# DRV8301.net
KiCad netlist of a schematic drawn in Altium Designer
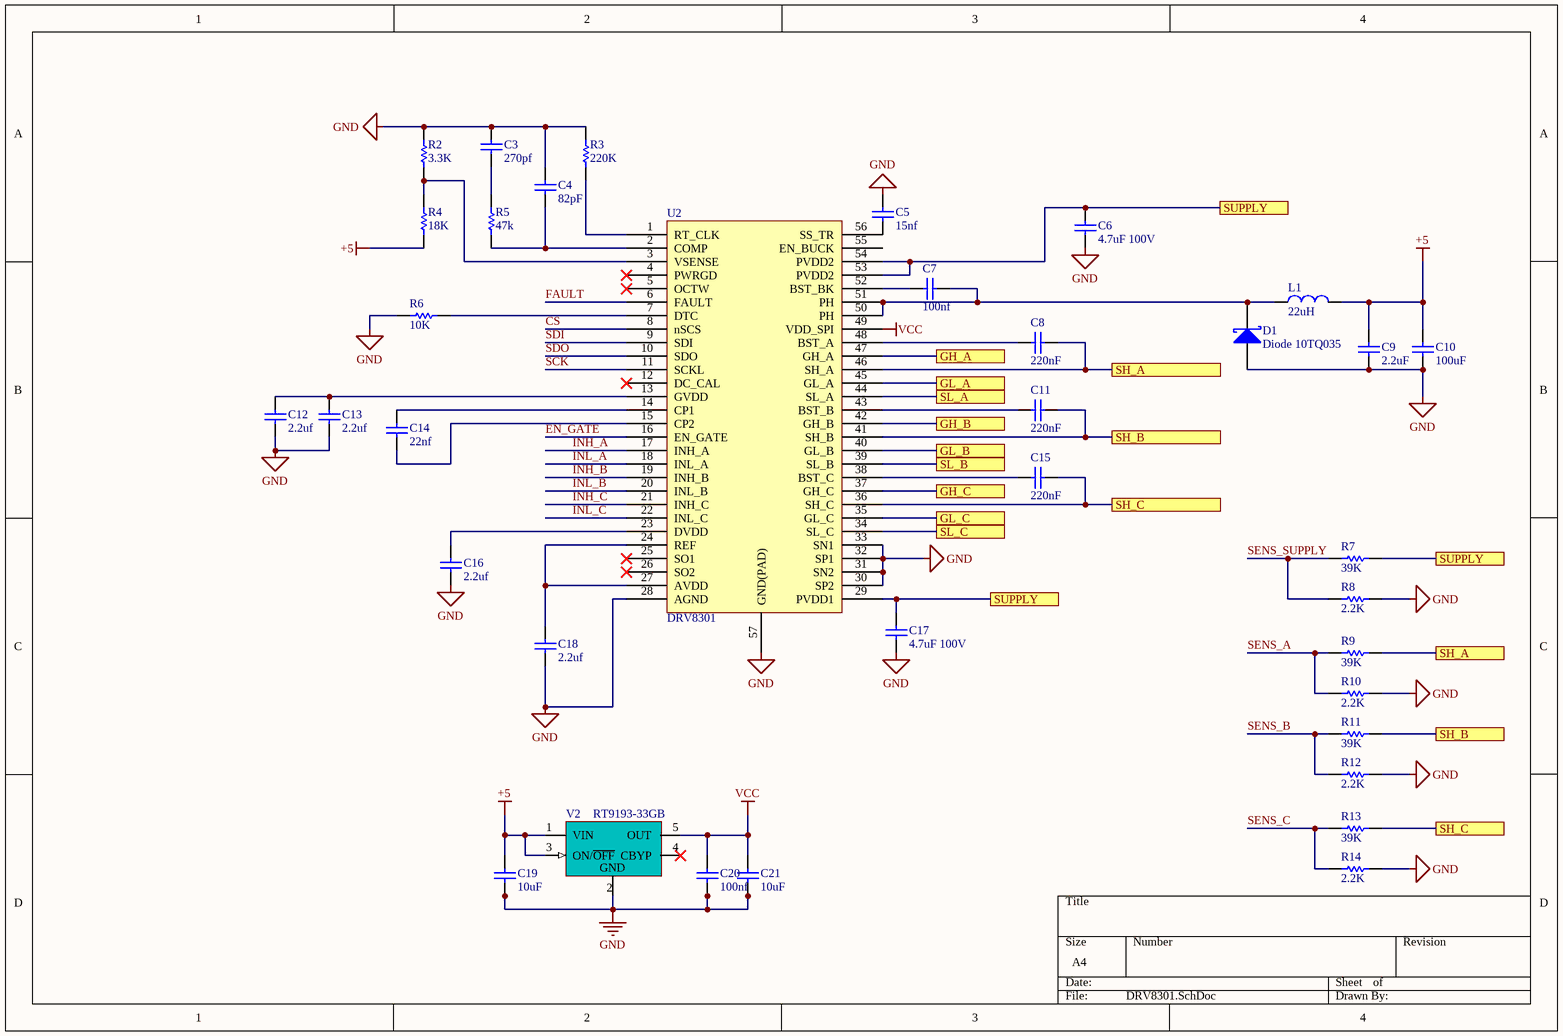
[diagram p0: DRV8301.SchDoc]

(export (version "E")
  (design (tool "Eeschema 10.0.6"))
  (components
    (comp (ref "C3")
      (value "270pf")
      (footprint "0603-1")
      (description "Capacitor")
      (fields (field (name "PUBLISHER") "Altium Limited"))
      (libsource (lib "My Footprint") (part "CAP"))
    )
    (comp (ref "C4")
      (value "82pF")
      (footprint "0603-1")
      (description "Capacitor")
      (fields (field (name "PUBLISHER") "Altium Limited"))
      (libsource (lib "My Footprint") (part "CAP"))
    )
    (comp (ref "C5")
      (value "15nf")
      (footprint "0603-1")
      (description "Capacitor")
      (fields (field (name "PUBLISHER") "Altium Limited"))
      (libsource (lib "My Footprint") (part "CAP"))
    )
    (comp (ref "C6")
      (value "4.7uF 100V")
      (footprint "0603-1")
      (description "Capacitor")
      (fields (field (name "PUBLISHER") "Altium Limited"))
      (libsource (lib "My Footprint") (part "CAP"))
    )
    (comp (ref "C7")
      (value "100nf")
      (footprint "0603-1")
      (description "Capacitor")
      (fields (field (name "PUBLISHER") "Altium Limited"))
      (libsource (lib "My Footprint") (part "CAP"))
    )
    (comp (ref "C8")
      (value "220nF")
      (footprint "0603-1")
      (description "Capacitor")
      (fields (field (name "PUBLISHER") "Altium Limited"))
      (libsource (lib "My Footprint") (part "CAP"))
    )
    (comp (ref "C9")
      (value "2.2uF")
      (footprint "0603-1")
      (description "Capacitor")
      (fields (field (name "PUBLISHER") "Altium Limited"))
      (libsource (lib "My Footprint") (part "CAP"))
    )
    (comp (ref "C10")
      (value "100uF")
      (footprint "0603-1")
      (description "Capacitor")
      (fields (field (name "PUBLISHER") "Altium Limited"))
      (libsource (lib "My Footprint") (part "CAP"))
    )
    (comp (ref "C11")
      (value "220nF")
      (footprint "0603-1")
      (description "Capacitor")
      (fields (field (name "PUBLISHER") "Altium Limited"))
      (libsource (lib "My Footprint") (part "CAP"))
    )
    (comp (ref "C12")
      (value "2.2uf")
      (footprint "0603-1")
      (description "Capacitor")
      (fields (field (name "PUBLISHER") "Altium Limited"))
      (libsource (lib "My Footprint") (part "CAP"))
    )
    (comp (ref "C13")
      (value "2.2uf")
      (footprint "0603-1")
      (description "Capacitor")
      (fields (field (name "PUBLISHER") "Altium Limited"))
      (libsource (lib "My Footprint") (part "CAP"))
    )
    (comp (ref "C14")
      (value "22nf")
      (footprint "0603-1")
      (description "Capacitor")
      (fields (field (name "PUBLISHER") "Altium Limited"))
      (libsource (lib "My Footprint") (part "CAP"))
    )
    (comp (ref "C15")
      (value "220nF")
      (footprint "0603-1")
      (description "Capacitor")
      (fields (field (name "PUBLISHER") "Altium Limited"))
      (libsource (lib "My Footprint") (part "CAP"))
    )
    (comp (ref "C16")
      (value "2.2uf")
      (footprint "0603-1")
      (description "Capacitor")
      (fields (field (name "PUBLISHER") "Altium Limited"))
      (libsource (lib "My Footprint") (part "CAP"))
    )
    (comp (ref "C17")
      (value "4.7uF 100V")
      (footprint "1206")
      (description "Capacitor")
      (fields (field (name "PUBLISHER") "Altium Limited"))
      (libsource (lib "My Footprint") (part "CAP"))
    )
    (comp (ref "C18")
      (value "2.2uf")
      (footprint "0603-1")
      (description "Capacitor")
      (fields (field (name "PUBLISHER") "Altium Limited"))
      (libsource (lib "My Footprint") (part "CAP"))
    )
    (comp (ref "C19")
      (value "10uF")
      (footprint "0805-1")
      (description "Capacitor")
      (fields (field (name "PUBLISHER") "Altium Limited"))
      (libsource (lib "My Footprint") (part "CAP"))
    )
    (comp (ref "C20")
      (value "100nf")
      (footprint "0603-1")
      (description "Capacitor")
      (fields (field (name "PUBLISHER") "Altium Limited"))
      (libsource (lib "My Footprint") (part "CAP"))
    )
    (comp (ref "C21")
      (value "10uF")
      (footprint "0805-1")
      (description "Capacitor")
      (fields (field (name "PUBLISHER") "Altium Limited"))
      (libsource (lib "My Footprint") (part "CAP"))
    )
    (comp (ref "D1")
      (value "Diode 10TQ035")
      (footprint "LC-SMA(DO-214AC)_S1")
      (description "Schottky Rectifier")
      (fields (field (name "PUBLISHER") "Altium Limited"))
      (libsource (lib "Miscellaneous Devices") (part "Diode 10TQ035"))
    )
    (comp (ref "L1")
      (value "22uH")
      (footprint "L-SMD-7")
      (libsource (lib "My Footprint") (part "L_Inductance"))
    )
    (comp (ref "R2")
      (value "3.3K")
      (footprint "0603-1")
      (description "Resistor")
      (fields (field (name "PUBLISHER") "Altium Limited"))
      (libsource (lib "My Footprint") (part "RES"))
    )
    (comp (ref "R3")
      (value "220K")
      (footprint "0603-1")
      (description "Resistor")
      (fields (field (name "PUBLISHER") "Altium Limited"))
      (libsource (lib "My Footprint") (part "RES"))
    )
    (comp (ref "R4")
      (value "18K")
      (footprint "0603-1")
      (description "Resistor")
      (fields (field (name "PUBLISHER") "Altium Limited"))
      (libsource (lib "My Footprint") (part "RES"))
    )
    (comp (ref "R5")
      (value "47k")
      (footprint "0603-1")
      (description "Resistor")
      (fields (field (name "PUBLISHER") "Altium Limited"))
      (libsource (lib "My Footprint") (part "RES"))
    )
    (comp (ref "R6")
      (value "10K")
      (footprint "0603-1")
      (description "Resistor")
      (fields (field (name "PUBLISHER") "Altium Limited"))
      (libsource (lib "My Footprint") (part "RES"))
    )
    (comp (ref "R7")
      (value "39K")
      (footprint "0603-1")
      (description "Resistor")
      (fields (field (name "PUBLISHER") "Altium Limited"))
      (libsource (lib "My Footprint") (part "RES"))
    )
    (comp (ref "R8")
      (value "2.2K")
      (footprint "0603-1")
      (description "Resistor")
      (fields (field (name "PUBLISHER") "Altium Limited"))
      (libsource (lib "My Footprint") (part "RES"))
    )
    (comp (ref "R9")
      (value "39K")
      (footprint "0603-1")
      (description "Resistor")
      (fields (field (name "PUBLISHER") "Altium Limited"))
      (libsource (lib "My Footprint") (part "RES"))
    )
    (comp (ref "R10")
      (value "2.2K")
      (footprint "0603-1")
      (description "Resistor")
      (fields (field (name "PUBLISHER") "Altium Limited"))
      (libsource (lib "My Footprint") (part "RES"))
    )
    (comp (ref "R11")
      (value "39K")
      (footprint "0603-1")
      (description "Resistor")
      (fields (field (name "PUBLISHER") "Altium Limited"))
      (libsource (lib "My Footprint") (part "RES"))
    )
    (comp (ref "R12")
      (value "2.2K")
      (footprint "0603-1")
      (description "Resistor")
      (fields (field (name "PUBLISHER") "Altium Limited"))
      (libsource (lib "My Footprint") (part "RES"))
    )
    (comp (ref "R13")
      (value "39K")
      (footprint "0603-1")
      (description "Resistor")
      (fields (field (name "PUBLISHER") "Altium Limited"))
      (libsource (lib "My Footprint") (part "RES"))
    )
    (comp (ref "R14")
      (value "2.2K")
      (footprint "0603-1")
      (description "Resistor")
      (fields (field (name "PUBLISHER") "Altium Limited"))
      (libsource (lib "My Footprint") (part "RES"))
    )
    (comp (ref "U2") (value "DRV8301") (footprint "DRV8301") (libsource (lib "VESC6 V1.0") (part "DRV8301")))
    (comp (ref "V2")
      (value "RT9193-33GB")
      (footprint "SOT23-5")
      (description "3.3V 300mA LDO Regulator,SOT-23-5")
      (fields
        (field (name "MANUFACTURER") "National Semiconductor")
        (field (name "MANUFACTURER PART NUMBER") "LP2992AIM5-3.3/NOPB")
      )
      (libsource (lib "naze32_sch_lb") (part "LP2985-3.3"))
    )
  )
  (nets
    (net (code "1") (name "+5") (class "Default")
      (node (ref "C10") (pin "1") (pinfunction "1_1") (pintype "passive"))
      (node (ref "C19") (pin "2") (pinfunction "2_2") (pintype "passive"))
      (node (ref "C9") (pin "1") (pinfunction "1_1") (pintype "passive"))
      (node (ref "L1") (pin "2") (pinfunction "2_2") (pintype "passive"))
      (node (ref "R4") (pin "1") (pinfunction "1_1") (pintype "passive"))
      (node (ref "V2") (pin "1") (pinfunction "VIN_1") (pintype "power_in"))
      (node (ref "V2") (pin "3") (pinfunction "ON/~{OFF}_3") (pintype "input"))
    )
    (net (code "2") (name "/CS") (class "Default")
      (node (ref "U2") (pin "8") (pinfunction "nSCS_8") (pintype "passive"))
    )
    (net (code "3") (name "/EN_GATE") (class "Default")
      (node (ref "U2") (pin "16") (pinfunction "EN_GATE_16") (pintype "passive"))
    )
    (net (code "4") (name "/FAULT") (class "Default")
      (node (ref "U2") (pin "6") (pinfunction "FAULT_6") (pintype "passive"))
    )
    (net (code "5") (name "/GH_A") (class "Default")
      (node (ref "U2") (pin "47") (pinfunction "GH_A_47") (pintype "passive"))
    )
    (net (code "6") (name "/GH_B") (class "Default")
      (node (ref "U2") (pin "42") (pinfunction "GH_B_42") (pintype "passive"))
    )
    (net (code "7") (name "/GH_C") (class "Default")
      (node (ref "U2") (pin "37") (pinfunction "GH_C_37") (pintype "passive"))
    )
    (net (code "8") (name "/GL_A") (class "Default")
      (node (ref "U2") (pin "45") (pinfunction "GL_A_45") (pintype "passive"))
    )
    (net (code "9") (name "/GL_B") (class "Default")
      (node (ref "U2") (pin "40") (pinfunction "GL_B_40") (pintype "passive"))
    )
    (net (code "10") (name "/GL_C") (class "Default")
      (node (ref "U2") (pin "35") (pinfunction "GL_C_35") (pintype "passive"))
    )
    (net (code "11") (name "/INH_A") (class "Default")
      (node (ref "U2") (pin "17") (pinfunction "INH_A_17") (pintype "passive"))
    )
    (net (code "12") (name "/INH_B") (class "Default")
      (node (ref "U2") (pin "19") (pinfunction "INH_B_19") (pintype "passive"))
    )
    (net (code "13") (name "/INH_C") (class "Default")
      (node (ref "U2") (pin "21") (pinfunction "INH_C_21") (pintype "passive"))
    )
    (net (code "14") (name "/INL_A") (class "Default")
      (node (ref "U2") (pin "18") (pinfunction "INL_A_18") (pintype "passive"))
    )
    (net (code "15") (name "/INL_B") (class "Default")
      (node (ref "U2") (pin "20") (pinfunction "INL_B_20") (pintype "passive"))
    )
    (net (code "16") (name "/INL_C") (class "Default")
      (node (ref "U2") (pin "22") (pinfunction "INL_C_22") (pintype "passive"))
    )
    (net (code "17") (name "/SCK") (class "Default")
      (node (ref "U2") (pin "11") (pinfunction "SCKL_11") (pintype "passive"))
    )
    (net (code "18") (name "/SDI") (class "Default")
      (node (ref "U2") (pin "9") (pinfunction "SDI_9") (pintype "passive"))
    )
    (net (code "19") (name "/SDO") (class "Default")
      (node (ref "U2") (pin "10") (pinfunction "SDO_10") (pintype "passive"))
    )
    (net (code "20") (name "/SENS_A") (class "Default")
      (node (ref "R10") (pin "2") (pinfunction "2_2") (pintype "passive"))
      (node (ref "R9") (pin "2") (pinfunction "2_2") (pintype "passive"))
    )
    (net (code "21") (name "/SENS_B") (class "Default")
      (node (ref "R11") (pin "2") (pinfunction "2_2") (pintype "passive"))
      (node (ref "R12") (pin "2") (pinfunction "2_2") (pintype "passive"))
    )
    (net (code "22") (name "/SENS_C") (class "Default")
      (node (ref "R13") (pin "2") (pinfunction "2_2") (pintype "passive"))
      (node (ref "R14") (pin "2") (pinfunction "2_2") (pintype "passive"))
    )
    (net (code "23") (name "/SENS_SUPPLY") (class "Default")
      (node (ref "R7") (pin "2") (pinfunction "2_2") (pintype "passive"))
      (node (ref "R8") (pin "2") (pinfunction "2_2") (pintype "passive"))
    )
    (net (code "24") (name "/SH_A") (class "Default")
      (node (ref "C8") (pin "1") (pinfunction "1_1") (pintype "passive"))
      (node (ref "R9") (pin "1") (pinfunction "1_1") (pintype "passive"))
      (node (ref "U2") (pin "46") (pinfunction "SH_A_46") (pintype "passive"))
    )
    (net (code "25") (name "/SH_B") (class "Default")
      (node (ref "C11") (pin "1") (pinfunction "1_1") (pintype "passive"))
      (node (ref "R11") (pin "1") (pinfunction "1_1") (pintype "passive"))
      (node (ref "U2") (pin "41") (pinfunction "SH_B_41") (pintype "passive"))
    )
    (net (code "26") (name "/SH_C") (class "Default")
      (node (ref "C15") (pin "1") (pinfunction "1_1") (pintype "passive"))
      (node (ref "R13") (pin "1") (pinfunction "1_1") (pintype "passive"))
      (node (ref "U2") (pin "36") (pinfunction "SH_C_36") (pintype "passive"))
    )
    (net (code "27") (name "/SL_A") (class "Default")
      (node (ref "U2") (pin "44") (pinfunction "SL_A_44") (pintype "passive"))
    )
    (net (code "28") (name "/SL_B") (class "Default")
      (node (ref "U2") (pin "39") (pinfunction "SL_B_39") (pintype "passive"))
    )
    (net (code "29") (name "/SL_C") (class "Default")
      (node (ref "U2") (pin "34") (pinfunction "SL_C_34") (pintype "passive"))
    )
    (net (code "30") (name "/SUPPLY") (class "Default")
      (node (ref "C17") (pin "2") (pinfunction "2_2") (pintype "passive"))
      (node (ref "C6") (pin "1") (pinfunction "1_1") (pintype "passive"))
      (node (ref "R7") (pin "1") (pinfunction "1_1") (pintype "passive"))
      (node (ref "U2") (pin "29") (pinfunction "PVDD1_29") (pintype "passive"))
      (node (ref "U2") (pin "53") (pinfunction "PVDD2_53") (pintype "passive"))
      (node (ref "U2") (pin "54") (pinfunction "PVDD2_54") (pintype "passive"))
    )
    (net (code "31") (name "GND") (class "Default")
      (node (ref "C10") (pin "2") (pinfunction "2_2") (pintype "passive"))
      (node (ref "C12") (pin "1") (pinfunction "1_1") (pintype "passive"))
      (node (ref "C13") (pin "1") (pinfunction "1_1") (pintype "passive"))
      (node (ref "C16") (pin "1") (pinfunction "1_1") (pintype "passive"))
      (node (ref "C17") (pin "1") (pinfunction "1_1") (pintype "passive"))
      (node (ref "C18") (pin "1") (pinfunction "1_1") (pintype "passive"))
      (node (ref "C19") (pin "1") (pinfunction "1_1") (pintype "passive"))
      (node (ref "C20") (pin "1") (pinfunction "1_1") (pintype "passive"))
      (node (ref "C21") (pin "1") (pinfunction "1_1") (pintype "passive"))
      (node (ref "C3") (pin "2") (pinfunction "2_2") (pintype "passive"))
      (node (ref "C4") (pin "2") (pinfunction "2_2") (pintype "passive"))
      (node (ref "C5") (pin "2") (pinfunction "2_2") (pintype "passive"))
      (node (ref "C6") (pin "2") (pinfunction "2_2") (pintype "passive"))
      (node (ref "C9") (pin "2") (pinfunction "2_2") (pintype "passive"))
      (node (ref "D1") (pin "2") (pinfunction "A_2") (pintype "passive"))
      (node (ref "R10") (pin "1") (pinfunction "1_1") (pintype "passive"))
      (node (ref "R12") (pin "1") (pinfunction "1_1") (pintype "passive"))
      (node (ref "R14") (pin "1") (pinfunction "1_1") (pintype "passive"))
      (node (ref "R2") (pin "2") (pinfunction "2_2") (pintype "passive"))
      (node (ref "R3") (pin "2") (pinfunction "2_2") (pintype "passive"))
      (node (ref "R6") (pin "2") (pinfunction "2_2") (pintype "passive"))
      (node (ref "R8") (pin "1") (pinfunction "1_1") (pintype "passive"))
      (node (ref "U2") (pin "28") (pinfunction "AGND_28") (pintype "passive"))
      (node (ref "U2") (pin "30") (pinfunction "SP2_30") (pintype "passive"))
      (node (ref "U2") (pin "31") (pinfunction "SN2_31") (pintype "passive"))
      (node (ref "U2") (pin "32") (pinfunction "SP1_32") (pintype "passive"))
      (node (ref "U2") (pin "33") (pinfunction "SN1_33") (pintype "passive"))
      (node (ref "U2") (pin "57") (pinfunction "GND(PAD)_57") (pintype "passive"))
      (node (ref "V2") (pin "2") (pinfunction "GND_2") (pintype "power_in"))
    )
    (net (code "32") (name "Net-(C3-Pad1)") (class "Default")
      (node (ref "C3") (pin "1") (pinfunction "1_1") (pintype "passive"))
      (node (ref "R5") (pin "2") (pinfunction "2_2") (pintype "passive"))
    )
    (net (code "33") (name "Net-(D1-K)") (class "Default")
      (node (ref "C7") (pin "1") (pinfunction "1_1") (pintype "passive"))
      (node (ref "D1") (pin "1") (pinfunction "K_1") (pintype "passive"))
      (node (ref "L1") (pin "1") (pinfunction "1_1") (pintype "passive"))
      (node (ref "U2") (pin "50") (pinfunction "PH_50") (pintype "passive"))
      (node (ref "U2") (pin "51") (pinfunction "PH_51") (pintype "passive"))
    )
    (net (code "34") (name "Net-(U2-AVDD)") (class "Default")
      (node (ref "C18") (pin "2") (pinfunction "2_2") (pintype "passive"))
      (node (ref "U2") (pin "24") (pinfunction "REF_24") (pintype "passive"))
      (node (ref "U2") (pin "27") (pinfunction "AVDD_27") (pintype "passive"))
    )
    (net (code "35") (name "Net-(U2-BST_A)") (class "Default")
      (node (ref "C8") (pin "2") (pinfunction "2_2") (pintype "passive"))
      (node (ref "U2") (pin "48") (pinfunction "BST_A_48") (pintype "passive"))
    )
    (net (code "36") (name "Net-(U2-BST_B)") (class "Default")
      (node (ref "C11") (pin "2") (pinfunction "2_2") (pintype "passive"))
      (node (ref "U2") (pin "43") (pinfunction "BST_B_43") (pintype "passive"))
    )
    (net (code "37") (name "Net-(U2-BST_BK)") (class "Default")
      (node (ref "C7") (pin "2") (pinfunction "2_2") (pintype "passive"))
      (node (ref "U2") (pin "52") (pinfunction "BST_BK_52") (pintype "passive"))
    )
    (net (code "38") (name "Net-(U2-BST_C)") (class "Default")
      (node (ref "C15") (pin "2") (pinfunction "2_2") (pintype "passive"))
      (node (ref "U2") (pin "38") (pinfunction "BST_C_38") (pintype "passive"))
    )
    (net (code "39") (name "Net-(U2-COMP)") (class "Default")
      (node (ref "C4") (pin "1") (pinfunction "1_1") (pintype "passive"))
      (node (ref "R5") (pin "1") (pinfunction "1_1") (pintype "passive"))
      (node (ref "U2") (pin "2") (pinfunction "COMP_2") (pintype "passive"))
    )
    (net (code "40") (name "Net-(U2-CP1)") (class "Default")
      (node (ref "C14") (pin "2") (pinfunction "2_2") (pintype "passive"))
      (node (ref "U2") (pin "14") (pinfunction "CP1_14") (pintype "passive"))
    )
    (net (code "41") (name "Net-(U2-CP2)") (class "Default")
      (node (ref "C14") (pin "1") (pinfunction "1_1") (pintype "passive"))
      (node (ref "U2") (pin "15") (pinfunction "CP2_15") (pintype "passive"))
    )
    (net (code "42") (name "Net-(U2-DTC)") (class "Default")
      (node (ref "R6") (pin "1") (pinfunction "1_1") (pintype "passive"))
      (node (ref "U2") (pin "7") (pinfunction "DTC_7") (pintype "passive"))
    )
    (net (code "43") (name "Net-(U2-DVDD)") (class "Default")
      (node (ref "C16") (pin "2") (pinfunction "2_2") (pintype "passive"))
      (node (ref "U2") (pin "23") (pinfunction "DVDD_23") (pintype "passive"))
    )
    (net (code "44") (name "Net-(U2-GVDD)") (class "Default")
      (node (ref "C12") (pin "2") (pinfunction "2_2") (pintype "passive"))
      (node (ref "C13") (pin "2") (pinfunction "2_2") (pintype "passive"))
      (node (ref "U2") (pin "13") (pinfunction "GVDD_13") (pintype "passive"))
    )
    (net (code "45") (name "Net-(U2-RT_CLK)") (class "Default")
      (node (ref "R3") (pin "1") (pinfunction "1_1") (pintype "passive"))
      (node (ref "U2") (pin "1") (pinfunction "RT_CLK_1") (pintype "passive"))
    )
    (net (code "46") (name "Net-(U2-SS_TR)") (class "Default")
      (node (ref "C5") (pin "1") (pinfunction "1_1") (pintype "passive"))
      (node (ref "U2") (pin "56") (pinfunction "SS_TR_56") (pintype "passive"))
    )
    (net (code "47") (name "Net-(U2-VSENSE)") (class "Default")
      (node (ref "R2") (pin "1") (pinfunction "1_1") (pintype "passive"))
      (node (ref "R4") (pin "2") (pinfunction "2_2") (pintype "passive"))
      (node (ref "U2") (pin "3") (pinfunction "VSENSE_3") (pintype "passive"))
    )
    (net (code "48") (name "VCC") (class "Default")
      (node (ref "C20") (pin "2") (pinfunction "2_2") (pintype "passive"))
      (node (ref "C21") (pin "2") (pinfunction "2_2") (pintype "passive"))
      (node (ref "U2") (pin "49") (pinfunction "VDD_SPI_49") (pintype "passive"))
      (node (ref "V2") (pin "5") (pinfunction "OUT_5") (pintype "power_in"))
    )
    (net (code "49") (name "unconnected-(U2-DC_CAL-Pad12)") (class "Default")
      (node (ref "U2") (pin "12") (pinfunction "DC_CAL_12") (pintype "passive+no_connect"))
    )
    (net (code "50") (name "unconnected-(U2-EN_BUCK-Pad55)") (class "Default")
      (node (ref "U2") (pin "55") (pinfunction "EN_BUCK_55") (pintype "passive"))
    )
    (net (code "51") (name "unconnected-(U2-OCTW-Pad5)") (class "Default")
      (node (ref "U2") (pin "5") (pinfunction "OCTW_5") (pintype "passive+no_connect"))
    )
    (net (code "52") (name "unconnected-(U2-PWRGD-Pad4)") (class "Default")
      (node (ref "U2") (pin "4") (pinfunction "PWRGD_4") (pintype "passive+no_connect"))
    )
    (net (code "53") (name "unconnected-(U2-SO1-Pad25)") (class "Default")
      (node (ref "U2") (pin "25") (pinfunction "SO1_25") (pintype "passive+no_connect"))
    )
    (net (code "54") (name "unconnected-(U2-SO2-Pad26)") (class "Default")
      (node (ref "U2") (pin "26") (pinfunction "SO2_26") (pintype "passive+no_connect"))
    )
    (net (code "55") (name "unconnected-(V2-CBYP-Pad4)") (class "Default")
      (node (ref "V2") (pin "4") (pinfunction "CBYP_4") (pintype "passive+no_connect"))
    )
  )
)
